# nest_jtag_serial.net
KiCad netlist of a schematic drawn in Altium Designer
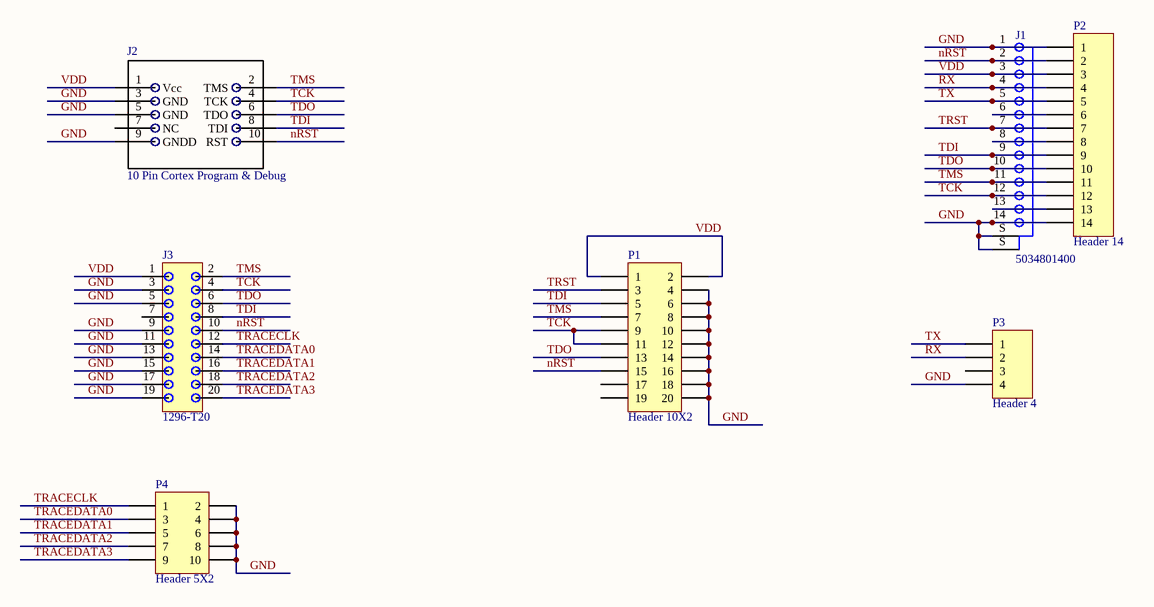
[diagram p0: nest_jtag_serial.SchDoc]

(export (version "E")
  (design (tool "Eeschema 10.0.6"))
  (components
    (comp (ref "J1")
      (value "5034801400")
      (footprint "FFC_14pin_5034801400")
      (description "CONN FFC FPC 14POS 0.50MM R/A")
      (libsource (lib "NewAE_AltiumLib") (part "CON14_2MNT"))
    )
    (comp (ref "J2")
      (value "10 Pin Cortex Program & Debug")
      (footprint "0.5mm_SMD_Header_5x2")
      (description "10 Pin Cortex Program & Debug 0.5mm pitch")
      (fields (field (name "PART NUMBER") "Cortex_Debug_Header_10Pin"))
      (libsource (lib "NewAE_AltiumLib") (part "Cortex_Debug_Header_10Pin"))
    )
    (comp (ref "J3")
      (value "1296-T20")
      (footprint "1296-T20")
      (description "Header, 20-pin, SMD, 0.05\"")
      (libsource (lib "NewAE_AltiumLib") (part "CON20_2ROW"))
    )
    (comp (ref "P1")
      (value "Header 10X2")
      (footprint "HDR2X10")
      (description "Header, 10-Pin, Dual row")
      (fields (field (name "PUBLISHER") "Altium Limited"))
      (libsource (lib "Miscellaneous Connectors") (part "Header 10X2"))
    )
    (comp (ref "P2")
      (value "Header 14")
      (footprint "HDR1X14")
      (description "Header, 14-Pin")
      (fields (field (name "PUBLISHER") "Altium Limited"))
      (libsource (lib "Miscellaneous Connectors") (part "Header 14"))
    )
    (comp (ref "P3")
      (value "Header 4")
      (footprint "HDR1X4")
      (description "Header, 4-Pin")
      (fields (field (name "PUBLISHER") "Altium Limited"))
      (libsource (lib "Miscellaneous Connectors") (part "Header 4"))
    )
    (comp (ref "P4")
      (value "Header 5X2")
      (footprint "HDR2X5")
      (description "Header, 5-Pin, Dual row")
      (fields (field (name "PUBLISHER") "Altium Limited"))
      (libsource (lib "Miscellaneous Connectors") (part "Header 5X2"))
    )
  )
  (nets
    (net (code "1") (name "/GND") (class "Default")
      (node (ref "J1") (pin "1") (pinfunction "1_1") (pintype "passive"))
      (node (ref "J1") (pin "14") (pinfunction "14_14") (pintype "passive"))
      (node (ref "J1") (pin "S") (pinfunction "MNT_S") (pintype "passive"))
      (node (ref "J2") (pin "3") (pinfunction "GND_3") (pintype "passive"))
      (node (ref "J2") (pin "5") (pinfunction "GND_5") (pintype "passive"))
      (node (ref "J2") (pin "9") (pinfunction "GNDD_9") (pintype "passive"))
      (node (ref "J3") (pin "11") (pinfunction "9_11") (pintype "passive"))
      (node (ref "J3") (pin "13") (pinfunction "9_13") (pintype "passive"))
      (node (ref "J3") (pin "15") (pinfunction "9_15") (pintype "passive"))
      (node (ref "J3") (pin "17") (pinfunction "9_17") (pintype "passive"))
      (node (ref "J3") (pin "19") (pinfunction "9_19") (pintype "passive"))
      (node (ref "J3") (pin "3") (pinfunction "3_3") (pintype "passive"))
      (node (ref "J3") (pin "5") (pinfunction "5_5") (pintype "passive"))
      (node (ref "J3") (pin "9") (pinfunction "9_9") (pintype "passive"))
      (node (ref "P1") (pin "10") (pinfunction "10_10") (pintype "passive"))
      (node (ref "P1") (pin "12") (pinfunction "12_12") (pintype "passive"))
      (node (ref "P1") (pin "14") (pinfunction "14_14") (pintype "passive"))
      (node (ref "P1") (pin "16") (pinfunction "16_16") (pintype "passive"))
      (node (ref "P1") (pin "18") (pinfunction "18_18") (pintype "passive"))
      (node (ref "P1") (pin "20") (pinfunction "20_20") (pintype "passive"))
      (node (ref "P1") (pin "4") (pinfunction "4_4") (pintype "passive"))
      (node (ref "P1") (pin "6") (pinfunction "6_6") (pintype "passive"))
      (node (ref "P1") (pin "8") (pinfunction "8_8") (pintype "passive"))
      (node (ref "P2") (pin "1") (pinfunction "1_1") (pintype "passive"))
      (node (ref "P2") (pin "14") (pinfunction "14_14") (pintype "passive"))
      (node (ref "P3") (pin "4") (pinfunction "4_4") (pintype "passive"))
      (node (ref "P4") (pin "10") (pinfunction "10_10") (pintype "passive"))
      (node (ref "P4") (pin "2") (pinfunction "2_2") (pintype "passive"))
      (node (ref "P4") (pin "4") (pinfunction "4_4") (pintype "passive"))
      (node (ref "P4") (pin "6") (pinfunction "6_6") (pintype "passive"))
      (node (ref "P4") (pin "8") (pinfunction "8_8") (pintype "passive"))
    )
    (net (code "2") (name "/RX") (class "Default")
      (node (ref "J1") (pin "4") (pinfunction "4_4") (pintype "passive"))
      (node (ref "P2") (pin "4") (pinfunction "4_4") (pintype "passive"))
      (node (ref "P3") (pin "2") (pinfunction "2_2") (pintype "passive"))
    )
    (net (code "3") (name "/TCK") (class "Default")
      (node (ref "J1") (pin "12") (pinfunction "12_12") (pintype "passive"))
      (node (ref "J2") (pin "4") (pinfunction "TCK_4") (pintype "passive"))
      (node (ref "J3") (pin "4") (pinfunction "4_4") (pintype "passive"))
      (node (ref "P1") (pin "11") (pinfunction "11_11") (pintype "passive"))
      (node (ref "P1") (pin "9") (pinfunction "9_9") (pintype "passive"))
      (node (ref "P2") (pin "12") (pinfunction "12_12") (pintype "passive"))
    )
    (net (code "4") (name "/TDI") (class "Default")
      (node (ref "J1") (pin "9") (pinfunction "9_9") (pintype "passive"))
      (node (ref "J2") (pin "8") (pinfunction "TDI_8") (pintype "passive"))
      (node (ref "J3") (pin "8") (pinfunction "8_8") (pintype "passive"))
      (node (ref "P1") (pin "5") (pinfunction "5_5") (pintype "passive"))
      (node (ref "P2") (pin "9") (pinfunction "9_9") (pintype "passive"))
    )
    (net (code "5") (name "/TDO") (class "Default")
      (node (ref "J1") (pin "10") (pinfunction "10_10") (pintype "passive"))
      (node (ref "J2") (pin "6") (pinfunction "TDO_6") (pintype "passive"))
      (node (ref "J3") (pin "6") (pinfunction "6_6") (pintype "passive"))
      (node (ref "P1") (pin "13") (pinfunction "13_13") (pintype "passive"))
      (node (ref "P2") (pin "10") (pinfunction "10_10") (pintype "passive"))
    )
    (net (code "6") (name "/TMS") (class "Default")
      (node (ref "J1") (pin "11") (pinfunction "11_11") (pintype "passive"))
      (node (ref "J2") (pin "2") (pinfunction "TMS_2") (pintype "passive"))
      (node (ref "J3") (pin "2") (pinfunction "2_2") (pintype "passive"))
      (node (ref "P1") (pin "7") (pinfunction "7_7") (pintype "passive"))
      (node (ref "P2") (pin "11") (pinfunction "11_11") (pintype "passive"))
    )
    (net (code "7") (name "/TRACECLK") (class "Default")
      (node (ref "J3") (pin "12") (pinfunction "10_12") (pintype "passive"))
      (node (ref "P4") (pin "1") (pinfunction "1_1") (pintype "passive"))
    )
    (net (code "8") (name "/TRACEDATA0") (class "Default")
      (node (ref "J3") (pin "14") (pinfunction "10_14") (pintype "passive"))
      (node (ref "P4") (pin "3") (pinfunction "3_3") (pintype "passive"))
    )
    (net (code "9") (name "/TRACEDATA1") (class "Default")
      (node (ref "J3") (pin "16") (pinfunction "10_16") (pintype "passive"))
      (node (ref "P4") (pin "5") (pinfunction "5_5") (pintype "passive"))
    )
    (net (code "10") (name "/TRACEDATA2") (class "Default")
      (node (ref "J3") (pin "18") (pinfunction "10_18") (pintype "passive"))
      (node (ref "P4") (pin "7") (pinfunction "7_7") (pintype "passive"))
    )
    (net (code "11") (name "/TRACEDATA3") (class "Default")
      (node (ref "J3") (pin "20") (pinfunction "10_20") (pintype "passive"))
      (node (ref "P4") (pin "9") (pinfunction "9_9") (pintype "passive"))
    )
    (net (code "12") (name "/TRST") (class "Default")
      (node (ref "J1") (pin "7") (pinfunction "7_7") (pintype "passive"))
      (node (ref "P1") (pin "3") (pinfunction "3_3") (pintype "passive"))
      (node (ref "P2") (pin "7") (pinfunction "7_7") (pintype "passive"))
    )
    (net (code "13") (name "/TX") (class "Default")
      (node (ref "J1") (pin "5") (pinfunction "5_5") (pintype "passive"))
      (node (ref "P2") (pin "5") (pinfunction "5_5") (pintype "passive"))
      (node (ref "P3") (pin "1") (pinfunction "1_1") (pintype "passive"))
    )
    (net (code "14") (name "/VDD") (class "Default")
      (node (ref "J1") (pin "3") (pinfunction "3_3") (pintype "passive"))
      (node (ref "J2") (pin "1") (pinfunction "Vcc_1") (pintype "passive"))
      (node (ref "J3") (pin "1") (pinfunction "1_1") (pintype "passive"))
      (node (ref "P1") (pin "1") (pinfunction "1_1") (pintype "passive"))
      (node (ref "P1") (pin "2") (pinfunction "2_2") (pintype "passive"))
      (node (ref "P2") (pin "3") (pinfunction "3_3") (pintype "passive"))
    )
    (net (code "15") (name "/nRST") (class "Default")
      (node (ref "J1") (pin "2") (pinfunction "2_2") (pintype "passive"))
      (node (ref "J2") (pin "10") (pinfunction "RST_10") (pintype "passive"))
      (node (ref "J3") (pin "10") (pinfunction "10_10") (pintype "passive"))
      (node (ref "P1") (pin "15") (pinfunction "15_15") (pintype "passive"))
      (node (ref "P2") (pin "2") (pinfunction "2_2") (pintype "passive"))
    )
    (net (code "16") (name "Net-(J1-Pad6)") (class "Default")
      (node (ref "J1") (pin "6") (pinfunction "6_6") (pintype "passive"))
      (node (ref "P2") (pin "6") (pinfunction "6_6") (pintype "passive"))
    )
    (net (code "17") (name "Net-(J1-Pad8)") (class "Default")
      (node (ref "J1") (pin "8") (pinfunction "8_8") (pintype "passive"))
      (node (ref "P2") (pin "8") (pinfunction "8_8") (pintype "passive"))
    )
    (net (code "18") (name "Net-(J1-Pad13)") (class "Default")
      (node (ref "J1") (pin "13") (pinfunction "13_13") (pintype "passive"))
      (node (ref "P2") (pin "13") (pinfunction "13_13") (pintype "passive"))
    )
    (net (code "19") (name "unconnected-(J2-NC-Pad7)") (class "Default")
      (node (ref "J2") (pin "7") (pinfunction "NC_7") (pintype "passive"))
    )
    (net (code "20") (name "unconnected-(J3-Pad7)") (class "Default")
      (node (ref "J3") (pin "7") (pinfunction "7_7") (pintype "passive"))
    )
    (net (code "21") (name "unconnected-(P1-Pad17)") (class "Default")
      (node (ref "P1") (pin "17") (pinfunction "17_17") (pintype "passive"))
    )
    (net (code "22") (name "unconnected-(P1-Pad19)") (class "Default")
      (node (ref "P1") (pin "19") (pinfunction "19_19") (pintype "passive"))
    )
    (net (code "23") (name "unconnected-(P3-Pad3)") (class "Default")
      (node (ref "P3") (pin "3") (pinfunction "3_3") (pintype "passive"))
    )
  )
)
